# b6s.net
KiCad netlist of a schematic drawn in EasyEDA Pro
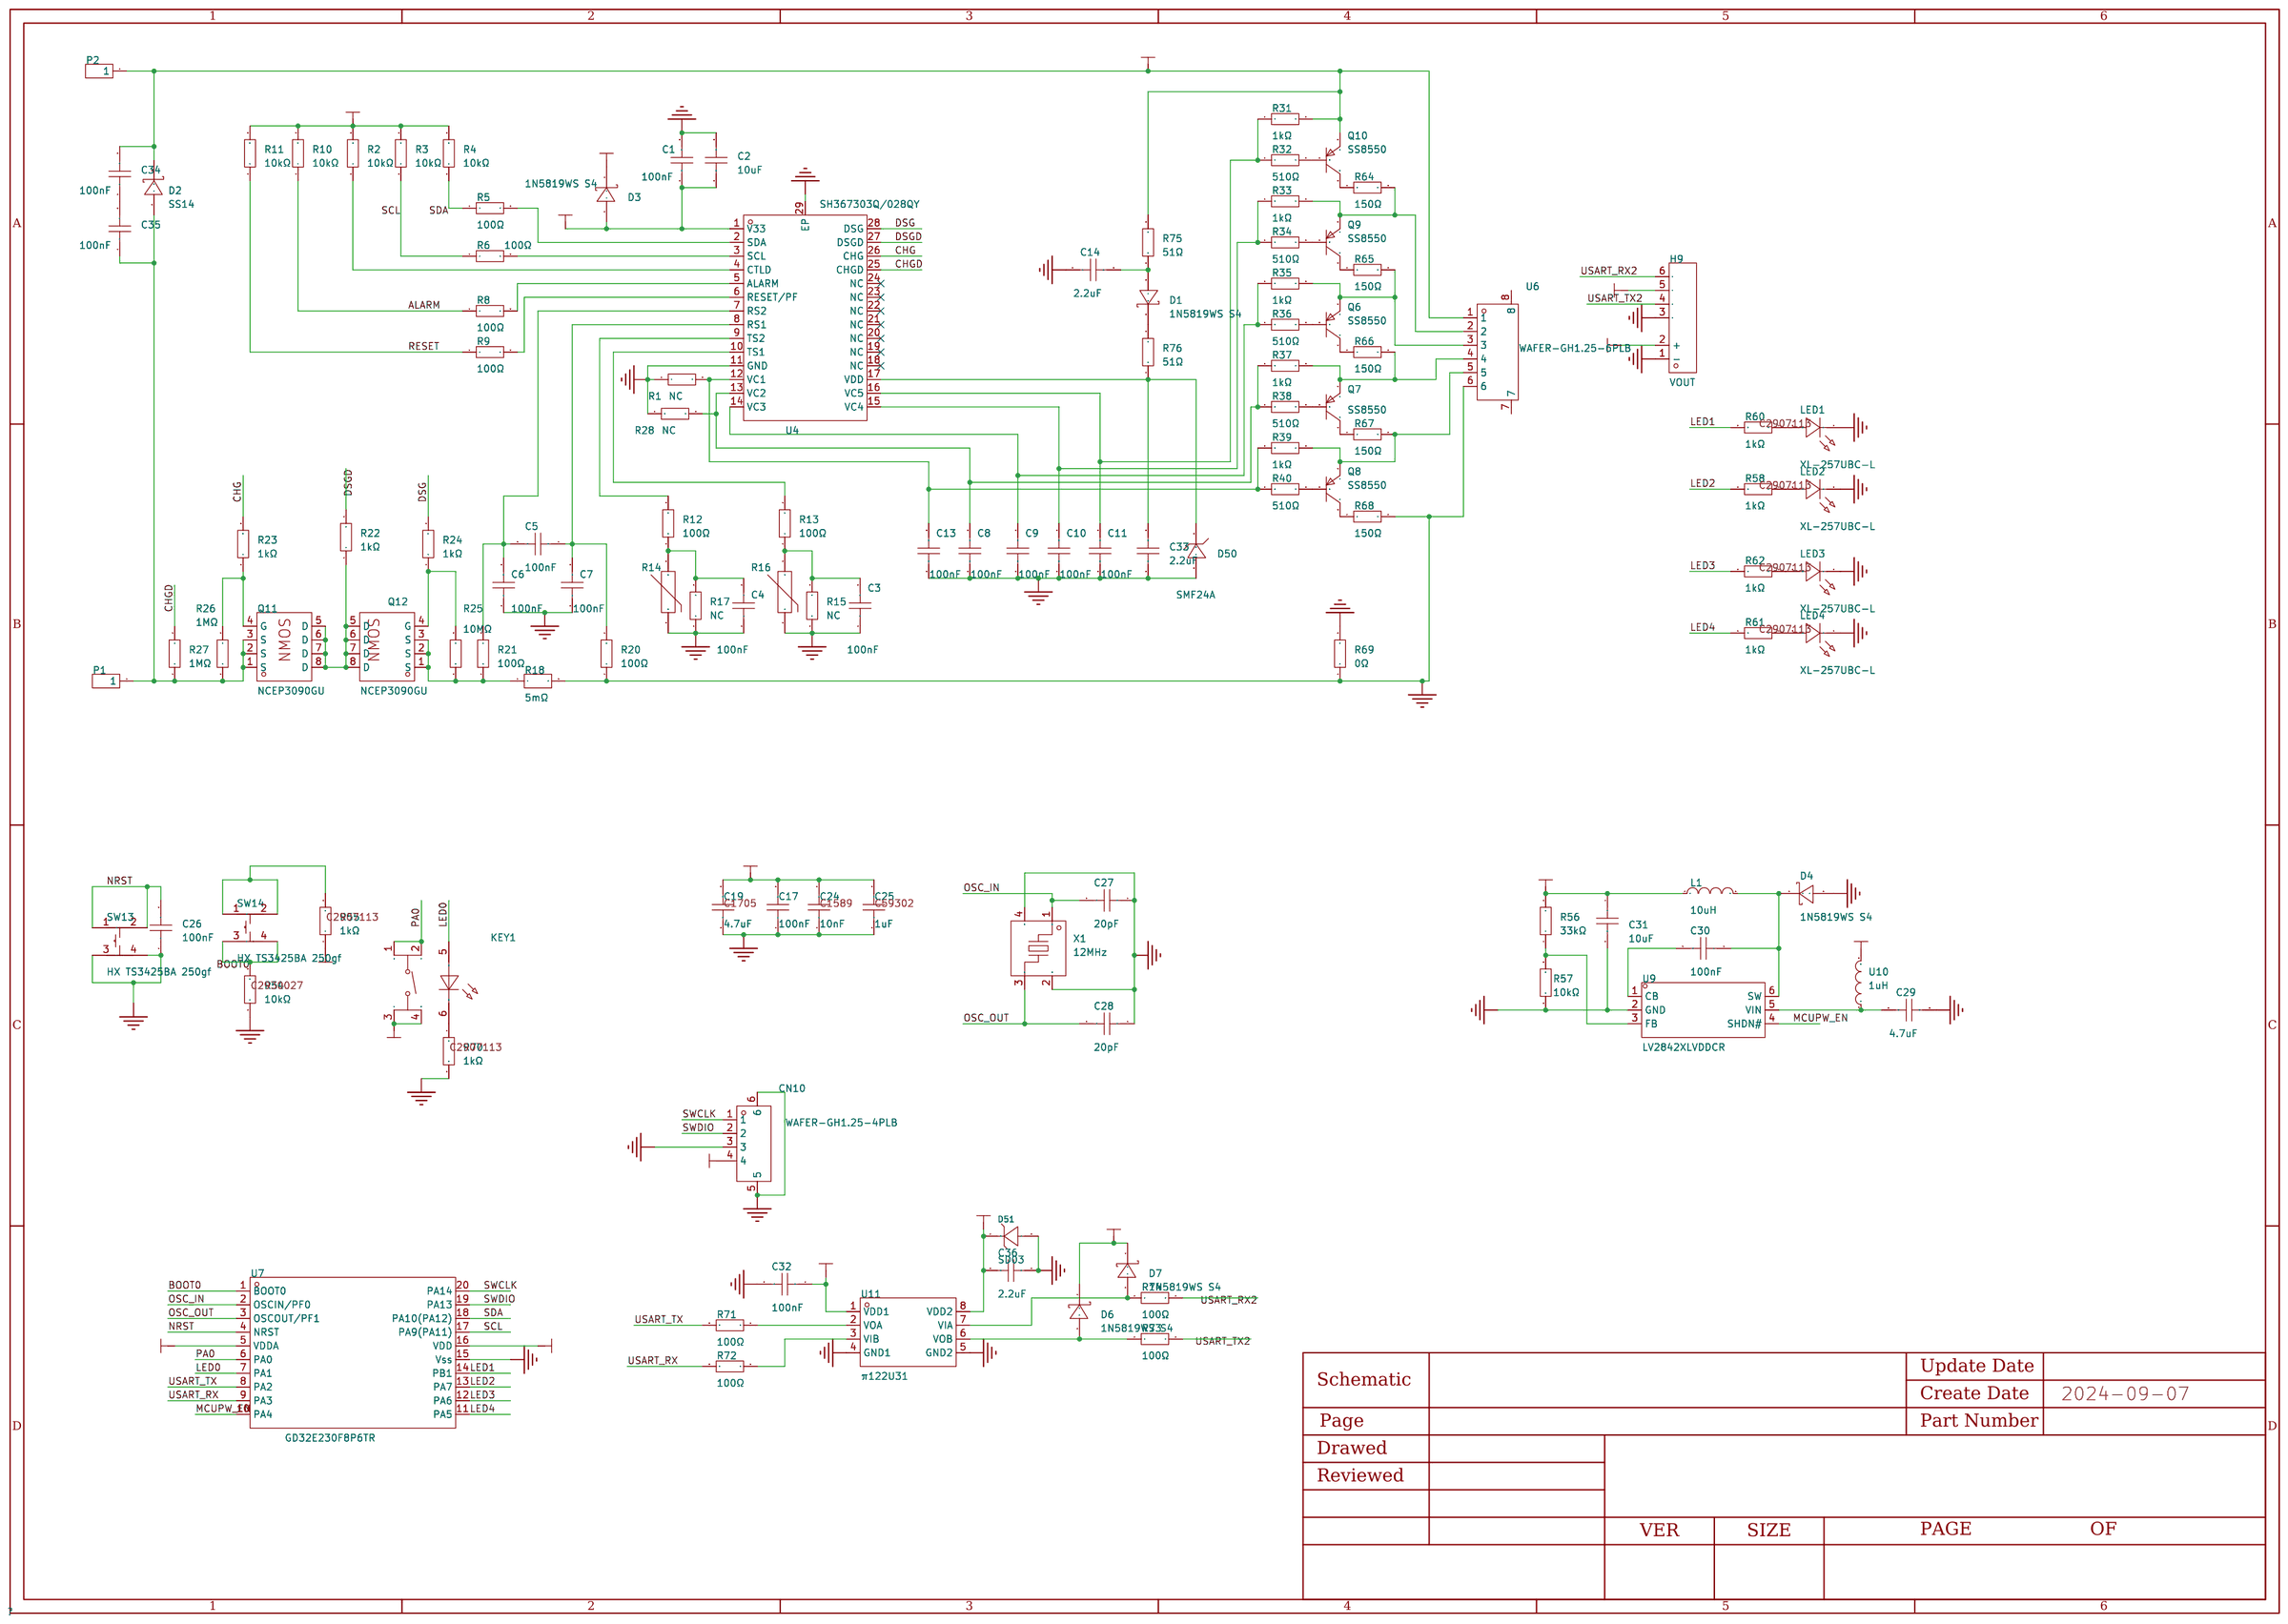
[diagram p0: schematic sheet]

(export (version "E")
  (design (tool "Eeschema 10.0.6"))
  (components
    (comp (ref "C1")
      (value "100nF")
      (footprint "easyedapro:C0603")
      (fields
        (field (name "Manufacturer Part") "CC0603KRX7R9BB104")
        (field (name "Manufacturer") "YAGEO(国巨)")
      )
      (libsource (lib "easyedapro") (part "CapAcitance"))
    )
    (comp (ref "C2")
      (value "10uF")
      (footprint "easyedapro:C0603")
      (fields
        (field (name "Manufacturer Part") "CL10A106MP8NNNC")
        (field (name "Manufacturer") "SAMSUNG(三星)")
      )
      (libsource (lib "easyedapro") (part "CapAcitance"))
    )
    (comp (ref "C3")
      (value "100nF")
      (footprint "easyedapro:C0603")
      (fields
        (field (name "Manufacturer Part") "CC0603KRX7R9BB104")
        (field (name "Manufacturer") "YAGEO(国巨)")
      )
      (libsource (lib "easyedapro") (part "CapAcitance"))
    )
    (comp (ref "C4")
      (value "100nF")
      (footprint "easyedapro:C0603")
      (fields
        (field (name "Manufacturer Part") "CC0603KRX7R9BB104")
        (field (name "Manufacturer") "YAGEO(国巨)")
      )
      (libsource (lib "easyedapro") (part "CapAcitance"))
    )
    (comp (ref "C5")
      (value "100nF")
      (footprint "easyedapro:C0603")
      (fields
        (field (name "Manufacturer Part") "CC0603KRX7R9BB104")
        (field (name "Manufacturer") "YAGEO(国巨)")
      )
      (libsource (lib "easyedapro") (part "CapAcitance"))
    )
    (comp (ref "C6")
      (value "100nF")
      (footprint "easyedapro:C0603")
      (fields
        (field (name "Manufacturer Part") "CC0603KRX7R9BB104")
        (field (name "Manufacturer") "YAGEO(国巨)")
      )
      (libsource (lib "easyedapro") (part "CapAcitance"))
    )
    (comp (ref "C7")
      (value "100nF")
      (footprint "easyedapro:C0603")
      (fields
        (field (name "Manufacturer Part") "CC0603KRX7R9BB104")
        (field (name "Manufacturer") "YAGEO(国巨)")
      )
      (libsource (lib "easyedapro") (part "CapAcitance"))
    )
    (comp (ref "C8")
      (value "100nF")
      (footprint "easyedapro:C0603")
      (fields
        (field (name "Manufacturer Part") "CC0603KRX7R9BB104")
        (field (name "Manufacturer") "YAGEO(国巨)")
      )
      (libsource (lib "easyedapro") (part "CapAcitance"))
    )
    (comp (ref "C9")
      (value "100nF")
      (footprint "easyedapro:C0603")
      (fields
        (field (name "Manufacturer Part") "CC0603KRX7R9BB104")
        (field (name "Manufacturer") "YAGEO(国巨)")
      )
      (libsource (lib "easyedapro") (part "CapAcitance"))
    )
    (comp (ref "C10")
      (value "100nF")
      (footprint "easyedapro:C0603")
      (fields
        (field (name "Manufacturer Part") "CC0603KRX7R9BB104")
        (field (name "Manufacturer") "YAGEO(国巨)")
      )
      (libsource (lib "easyedapro") (part "CapAcitance"))
    )
    (comp (ref "C11")
      (value "100nF")
      (footprint "easyedapro:C0603")
      (fields
        (field (name "Manufacturer Part") "CC0603KRX7R9BB104")
        (field (name "Manufacturer") "YAGEO(国巨)")
      )
      (libsource (lib "easyedapro") (part "CapAcitance"))
    )
    (comp (ref "C13")
      (value "100nF")
      (footprint "easyedapro:C0603")
      (fields
        (field (name "Manufacturer Part") "CC0603KRX7R9BB104")
        (field (name "Manufacturer") "YAGEO(国巨)")
      )
      (libsource (lib "easyedapro") (part "CapAcitance"))
    )
    (comp (ref "C14")
      (value "2.2uF")
      (footprint "easyedapro:C0603")
      (fields
        (field (name "Manufacturer Part") "CL21A225KBQNNNE")
        (field (name "Manufacturer") "SAMSUNG(三星)")
      )
      (libsource (lib "easyedapro") (part "CapAcitance"))
    )
    (comp (ref "C17")
      (value "100nF")
      (footprint "easyedapro:C0603")
      (fields
        (field (name "Manufacturer Part") "CC0603KRX7R9BB104")
        (field (name "Manufacturer") "YAGEO(国巨)")
      )
      (libsource (lib "easyedapro") (part "CapAcitance"))
    )
    (comp (ref "C19")
      (value "4.7uF")
      (footprint "easyedapro:C0603")
      (fields
        (field (name "Manufacturer Part") "CL10A475KP8NNNC")
        (field (name "Manufacturer") "SAMSUNG(三星)")
        (field (name "Supplier Part") "C1705")
      )
      (libsource (lib "easyedapro") (part "CapAcitance"))
    )
    (comp (ref "C24")
      (value "10nF")
      (footprint "easyedapro:C0603")
      (fields
        (field (name "Manufacturer Part") "CL10B103KB8NNNC")
        (field (name "Manufacturer") "SAMSUNG(三星)")
        (field (name "Supplier Part") "C1589")
      )
      (libsource (lib "easyedapro") (part "CapAcitance"))
    )
    (comp (ref "C25")
      (value "1uF")
      (footprint "easyedapro:C0603")
      (fields
        (field (name "Manufacturer Part") "0603B105K250NT")
        (field (name "Manufacturer") "FH(风华)")
        (field (name "Supplier Part") "C59302")
      )
      (libsource (lib "easyedapro") (part "CapAcitance"))
    )
    (comp (ref "C26")
      (value "100nF")
      (footprint "easyedapro:C0603")
      (fields
        (field (name "Manufacturer Part") "CC0603KRX7R9BB104")
        (field (name "Manufacturer") "YAGEO(国巨)")
      )
      (libsource (lib "easyedapro") (part "CapAcitance"))
    )
    (comp (ref "C27")
      (value "20pF")
      (footprint "easyedapro:C0603")
      (fields (field (name "Manufacturer Part") "0603CG200J500NT") (field (name "Manufacturer") "FH(风华)"))
      (libsource (lib "easyedapro") (part "CapAcitance"))
    )
    (comp (ref "C28")
      (value "20pF")
      (footprint "easyedapro:C0603")
      (fields (field (name "Manufacturer Part") "0603CG200J500NT") (field (name "Manufacturer") "FH(风华)"))
      (libsource (lib "easyedapro") (part "CapAcitance"))
    )
    (comp (ref "C29")
      (value "4.7uF")
      (footprint "easyedapro:C0603")
      (fields
        (field (name "Manufacturer Part") "CGA0805X7R475K350MT")
        (field (name "Manufacturer") "HRE(芯声)")
      )
      (libsource (lib "easyedapro") (part "CapAcitance"))
    )
    (comp (ref "C30")
      (value "100nF")
      (footprint "easyedapro:C0603")
      (fields
        (field (name "Manufacturer Part") "CC0603KRX7R9BB104")
        (field (name "Manufacturer") "YAGEO(国巨)")
      )
      (libsource (lib "easyedapro") (part "CapAcitance"))
    )
    (comp (ref "C31")
      (value "10uF")
      (footprint "easyedapro:C0603")
      (fields
        (field (name "Manufacturer Part") "CL10A106MP8NNNC")
        (field (name "Manufacturer") "SAMSUNG(三星)")
      )
      (libsource (lib "easyedapro") (part "CapAcitance"))
    )
    (comp (ref "C32")
      (value "100nF")
      (footprint "easyedapro:C0603")
      (fields
        (field (name "Manufacturer Part") "CC0603KRX7R9BB104")
        (field (name "Manufacturer") "YAGEO(国巨)")
      )
      (libsource (lib "easyedapro") (part "CapAcitance"))
    )
    (comp (ref "C33")
      (value "2.2uF")
      (footprint "easyedapro:C0603")
      (fields
        (field (name "Manufacturer Part") "CL21A225KBQNNNE")
        (field (name "Manufacturer") "SAMSUNG(三星)")
      )
      (libsource (lib "easyedapro") (part "CapAcitance"))
    )
    (comp (ref "C34")
      (value "100nF")
      (footprint "easyedapro:C0603")
      (fields
        (field (name "Manufacturer Part") "CC0603KRX7R9BB104")
        (field (name "Manufacturer") "YAGEO(国巨)")
      )
      (libsource (lib "easyedapro") (part "CapAcitance"))
    )
    (comp (ref "C35")
      (value "100nF")
      (footprint "easyedapro:C0603")
      (fields
        (field (name "Manufacturer Part") "CC0603KRX7R9BB104")
        (field (name "Manufacturer") "YAGEO(国巨)")
      )
      (libsource (lib "easyedapro") (part "CapAcitance"))
    )
    (comp (ref "C36")
      (value "2.2uF")
      (footprint "easyedapro:C0603")
      (fields
        (field (name "Manufacturer Part") "CL10A225KP8NNNC")
        (field (name "Manufacturer") "SAMSUNG(三星)")
      )
      (libsource (lib "easyedapro") (part "CapAcitance"))
    )
    (comp (ref "CN10")
      (value "WAFER-GH1.25-4PLB")
      (footprint "easyedapro:CONN-SMD_4P-P1.25_XUNPU_WAFER-GH1.25-4PLB")
      (description "插针结构:1x4P;间距:1.25mm;安装方式:立贴;参考系列:GH;总PIN数:4P;排数:1;每排PIN数:4;额定电流:1A;工作温度范围:-25°C~+85°C;")
      (fields (field (name "Manufacturer") "XUNPU(讯普)"))
      (libsource (lib "easyedapro") (part "WAFER-GH1.25-4PLB"))
    )
    (comp (ref "D1")
      (value "1N5819WS S4")
      (footprint "easyedapro:SOD-323_L1.8-W1.3-LS2.5-RD")
      (description "正向压降(Vf):600mV@1A;直流反向耐压(Vr):40V;平均整流电流(Io):1A;")
      (fields (field (name "Manufacturer") "JSMSEMI(杰盛微)"))
      (libsource (lib "easyedapro") (part "1N5819WS"))
    )
    (comp (ref "D2")
      (value "SS14")
      (footprint "easyedapro:SMA_L4.2-W2.6-LS5.3-RD")
      (description "二极管配置:独立式;正向压降(Vf):550mV@1A;直流反向耐压(Vr):40V;整流电流:1A;")
      (fields (field (name "Manufacturer") "MDD(辰达半导体)"))
      (libsource (lib "easyedapro") (part "SS14"))
    )
    (comp (ref "D3")
      (value "1N5819WS S4")
      (footprint "easyedapro:SOD-323_L1.8-W1.3-LS2.5-RD")
      (description "正向压降(Vf):600mV@1A;直流反向耐压(Vr):40V;平均整流电流(Io):1A;")
      (fields (field (name "Manufacturer") "JSMSEMI(杰盛微)"))
      (libsource (lib "easyedapro") (part "1N5819WS"))
    )
    (comp (ref "D4")
      (value "1N5819WS S4")
      (footprint "easyedapro:SOD-323_L1.8-W1.3-LS2.5-RD")
      (description "正向压降(Vf):600mV@1A;直流反向耐压(Vr):40V;平均整流电流(Io):1A;")
      (fields (field (name "Manufacturer") "JSMSEMI(杰盛微)"))
      (libsource (lib "easyedapro") (part "1N5819WS"))
    )
    (comp (ref "D6")
      (value "1N5819WS S4")
      (footprint "easyedapro:SOD-323_L1.8-W1.3-LS2.5-RD")
      (description "正向压降(Vf):600mV@1A;直流反向耐压(Vr):40V;平均整流电流(Io):1A;")
      (fields (field (name "Manufacturer") "JSMSEMI(杰盛微)"))
      (libsource (lib "easyedapro") (part "1N5819WS"))
    )
    (comp (ref "D7")
      (value "1N5819WS S4")
      (footprint "easyedapro:SOD-323_L1.8-W1.3-LS2.5-RD")
      (description "正向压降(Vf):600mV@1A;直流反向耐压(Vr):40V;平均整流电流(Io):1A;")
      (fields (field (name "Manufacturer") "JSMSEMI(杰盛微)"))
      (libsource (lib "easyedapro") (part "1N5819WS"))
    )
    (comp (ref "D50")
      (value "SMF24A")
      (footprint "easyedapro:SOD-123FL_L2.8-W1.9-LS3.7-RD")
      (description "反向截止电压(Vrwm):22V;最大钳位电压:35.5V;峰值脉冲电流(Ipp)@10/1000us:5.6A;击穿电压:24.4V;")
      (fields (field (name "Manufacturer") "TWGMC(台湾迪嘉)"))
      (libsource (lib "easyedapro") (part "SMF22A_C2943862"))
    )
    (comp (ref "D51")
      (value "SD03")
      (footprint "easyedapro:SOD-323_L1.8-W1.3-LS2.5-RD")
      (description "反向截止电压(Vrwm):3.3V;最大钳位电压:14V;峰值脉冲电流(Ipp)@10/1000us:20A;击穿电压:4V;")
      (fields (field (name "Manufacturer") "MDD"))
      (libsource (lib "easyedapro") (part "SD03_C502526"))
    )
    (comp (ref "H9")
      (value "VOUT")
      (footprint "easyedapro:AMSS_XT60_2+4")
      (libsource (lib "easyedapro") (part "AMSS_XT60_2+4"))
    )
    (comp (ref "KEY1")
      (value "~")
      (footprint "easyedapro:LED_BUTTON")
      (libsource (lib "easyedapro") (part "LED_BUTTON"))
    )
    (comp (ref "L1")
      (value "10uH")
      (footprint "easyedapro:L1206")
      (description "电感值:1uH;精度:±20%;额定电流:1.2A;饱和电流(Isat):-;直流电阻(DCR):150mΩ;")
      (fields (field (name "Manufacturer Part") "CMI321609X100KT") (field (name "Manufacturer") "FH(风华)"))
      (libsource (lib "easyedapro") (part "CMP321609UD1R0MT"))
    )
    (comp (ref "LED1")
      (value "XL-257UBC-L")
      (footprint "easyedapro:LED-TH_L5.0-W2.5-P2.54-FD_GREEN_XL-257SYGD-L")
      (fields (field (name "Manufacturer") "XINGLIGHT(成兴光)"))
      (libsource (lib "easyedapro") (part "XL-257UBC-L"))
    )
    (comp (ref "LED2")
      (value "XL-257UBC-L")
      (footprint "easyedapro:LED-TH_L5.0-W2.5-P2.54-FD_GREEN_XL-257SYGD-L")
      (fields (field (name "Manufacturer") "XINGLIGHT(成兴光)"))
      (libsource (lib "easyedapro") (part "XL-257UBC-L"))
    )
    (comp (ref "LED3")
      (value "XL-257UBC-L")
      (footprint "easyedapro:LED-TH_L5.0-W2.5-P2.54-FD_GREEN_XL-257SYGD-L")
      (fields (field (name "Manufacturer") "XINGLIGHT(成兴光)"))
      (libsource (lib "easyedapro") (part "XL-257UBC-L"))
    )
    (comp (ref "LED4")
      (value "XL-257UBC-L")
      (footprint "easyedapro:LED-TH_L5.0-W2.5-P2.54-FD_GREEN_XL-257SYGD-L")
      (fields (field (name "Manufacturer") "XINGLIGHT(成兴光)"))
      (libsource (lib "easyedapro") (part "XL-257UBC-L"))
    )
    (comp (ref "P1")
      (value "~")
      (footprint "easyedapro:Wire_14AWG")
      (libsource (lib "easyedapro") (part "Wire_14AWG"))
    )
    (comp (ref "P2")
      (value "~")
      (footprint "easyedapro:Wire_14AWG")
      (libsource (lib "easyedapro") (part "Wire_14AWG"))
    )
    (comp (ref "Q6")
      (value "SS8550")
      (footprint "easyedapro:SOT-23-3_L2.9-W1.3-P1.90-LS2.4-BR")
      (description "晶体管类型:PNP;集电极电流(Ic):1.5A;集射极击穿电压(Vceo):25V;功率(Pd):300mW;直流电流增益(hFE@Ic,Vce):120@100mA,1.0V;")
      (fields (field (name "Manufacturer") "宏迦橙"))
      (libsource (lib "easyedapro") (part "SS8550_C7420371"))
    )
    (comp (ref "Q7")
      (value "SS8550")
      (footprint "easyedapro:SOT-23-3_L2.9-W1.3-P1.90-LS2.4-BR")
      (description "晶体管类型:PNP;集电极电流(Ic):1.5A;集射极击穿电压(Vceo):25V;功率(Pd):300mW;直流电流增益(hFE@Ic,Vce):120@100mA,1.0V;")
      (fields (field (name "Manufacturer") "宏迦橙"))
      (libsource (lib "easyedapro") (part "SS8550_C7420371"))
    )
    (comp (ref "Q8")
      (value "SS8550")
      (footprint "easyedapro:SOT-23-3_L2.9-W1.3-P1.90-LS2.4-BR")
      (description "晶体管类型:PNP;集电极电流(Ic):1.5A;集射极击穿电压(Vceo):25V;功率(Pd):300mW;直流电流增益(hFE@Ic,Vce):120@100mA,1.0V;")
      (fields (field (name "Manufacturer") "宏迦橙"))
      (libsource (lib "easyedapro") (part "SS8550_C7420371"))
    )
    (comp (ref "Q9")
      (value "SS8550")
      (footprint "easyedapro:SOT-23-3_L2.9-W1.3-P1.90-LS2.4-BR")
      (description "晶体管类型:PNP;集电极电流(Ic):1.5A;集射极击穿电压(Vceo):25V;功率(Pd):300mW;直流电流增益(hFE@Ic,Vce):120@100mA,1.0V;")
      (fields (field (name "Manufacturer") "宏迦橙"))
      (libsource (lib "easyedapro") (part "SS8550_C7420371"))
    )
    (comp (ref "Q10")
      (value "SS8550")
      (footprint "easyedapro:SOT-23-3_L2.9-W1.3-P1.90-LS2.4-BR")
      (description "晶体管类型:PNP;集电极电流(Ic):1.5A;集射极击穿电压(Vceo):25V;功率(Pd):300mW;直流电流增益(hFE@Ic,Vce):120@100mA,1.0V;")
      (fields (field (name "Manufacturer") "宏迦橙"))
      (libsource (lib "easyedapro") (part "SS8550_C7420371"))
    )
    (comp (ref "Q11")
      (value "NCEP3090GU")
      (footprint "easyedapro:DFN-8_L5.8-W4.9-P1.27-LS6.1-BL-2")
      (fields (field (name "Manufacturer") "NCE(无锡新洁能)"))
      (libsource (lib "easyedapro") (part "NCEP3090GU"))
    )
    (comp (ref "Q12")
      (value "NCEP3090GU")
      (footprint "easyedapro:DFN-8_L5.8-W4.9-P1.27-LS6.1-BL-2")
      (fields (field (name "Manufacturer") "NCE(无锡新洁能)"))
      (libsource (lib "easyedapro") (part "NCEP3090GU"))
    )
    (comp (ref "R1") (value "NC") (footprint "easyedapro:R0805") (libsource (lib "easyedapro") (part "电阻")))
    (comp (ref "R2")
      (value "10kΩ")
      (footprint "easyedapro:R0805")
      (fields (field (name "Manufacturer Part") "FRC0603J103TS") (field (name "Manufacturer") "FOJAN(富捷)"))
      (libsource (lib "easyedapro") (part "电阻"))
    )
    (comp (ref "R3")
      (value "10kΩ")
      (footprint "easyedapro:R0805")
      (fields (field (name "Manufacturer Part") "FRC0603J103TS") (field (name "Manufacturer") "FOJAN(富捷)"))
      (libsource (lib "easyedapro") (part "电阻"))
    )
    (comp (ref "R4")
      (value "10kΩ")
      (footprint "easyedapro:R0805")
      (fields (field (name "Manufacturer Part") "FRC0603J103TS") (field (name "Manufacturer") "FOJAN(富捷)"))
      (libsource (lib "easyedapro") (part "电阻"))
    )
    (comp (ref "R5")
      (value "100Ω")
      (footprint "easyedapro:R0805")
      (fields (field (name "Manufacturer Part") "RC0603FR-07100RL") (field (name "Manufacturer") "YAGEO(国巨)"))
      (libsource (lib "easyedapro") (part "电阻"))
    )
    (comp (ref "R6")
      (value "100Ω")
      (footprint "easyedapro:R0805")
      (fields (field (name "Manufacturer Part") "RC0603FR-07100RL") (field (name "Manufacturer") "YAGEO(国巨)"))
      (libsource (lib "easyedapro") (part "电阻"))
    )
    (comp (ref "R8")
      (value "100Ω")
      (footprint "easyedapro:R0805")
      (fields (field (name "Manufacturer Part") "RC0603FR-07100RL") (field (name "Manufacturer") "YAGEO(国巨)"))
      (libsource (lib "easyedapro") (part "电阻"))
    )
    (comp (ref "R9")
      (value "100Ω")
      (footprint "easyedapro:R0805")
      (fields (field (name "Manufacturer Part") "RC0603FR-07100RL") (field (name "Manufacturer") "YAGEO(国巨)"))
      (libsource (lib "easyedapro") (part "电阻"))
    )
    (comp (ref "R10")
      (value "10kΩ")
      (footprint "easyedapro:R0805")
      (fields (field (name "Manufacturer Part") "FRC0603J103TS") (field (name "Manufacturer") "FOJAN(富捷)"))
      (libsource (lib "easyedapro") (part "电阻"))
    )
    (comp (ref "R11")
      (value "10kΩ")
      (footprint "easyedapro:R0805")
      (fields (field (name "Manufacturer Part") "FRC0603J103TS") (field (name "Manufacturer") "FOJAN(富捷)"))
      (libsource (lib "easyedapro") (part "电阻"))
    )
    (comp (ref "R12")
      (value "100Ω")
      (footprint "easyedapro:R0805")
      (fields (field (name "Manufacturer Part") "RC0603FR-07100RL") (field (name "Manufacturer") "YAGEO(国巨)"))
      (libsource (lib "easyedapro") (part "电阻"))
    )
    (comp (ref "R13")
      (value "100Ω")
      (footprint "easyedapro:R0805")
      (fields (field (name "Manufacturer Part") "RC0603FR-07100RL") (field (name "Manufacturer") "YAGEO(国巨)"))
      (libsource (lib "easyedapro") (part "电阻"))
    )
    (comp (ref "R14")
      (value "MF52A103F3950 (A1)")
      (footprint "easyedapro:RES-TH_L2.5-W2.5-P1.70-D0.3")
      (description "阻值(25°C):10kΩ;B值(25°C/50°C):3950K;电阻精度:±1%;功率:50mW;B值精度:±1%;最大稳态电流(25°C):-;")
      (fields (field (name "Manufacturer") "时恒"))
      (libsource (lib "easyedapro") (part "MF52A1103F3950(P334-4)"))
    )
    (comp (ref "R15") (value "NC") (footprint "easyedapro:R0805") (libsource (lib "easyedapro") (part "电阻")))
    (comp (ref "R16")
      (value "MF52A103F3950 (A1)")
      (footprint "easyedapro:RES-TH_L2.5-W2.5-P1.70-D0.3")
      (description "阻值(25°C):10kΩ;B值(25°C/50°C):3950K;电阻精度:±1%;功率:50mW;B值精度:±1%;最大稳态电流(25°C):-;")
      (fields (field (name "Manufacturer") "时恒"))
      (libsource (lib "easyedapro") (part "MF52A1103F3950(P334-4)"))
    )
    (comp (ref "R17") (value "NC") (footprint "easyedapro:R0805") (libsource (lib "easyedapro") (part "电阻")))
    (comp (ref "R18")
      (value "5mΩ")
      (footprint "easyedapro:RES-SMD_L6.4-W3.2-1")
      (description "电阻类型:采样电阻;阻值:5mΩ;精度:±1%;额定压降:-;功率:3W;温度系数:±50ppm/°C;安装方式:贴片;")
      (fields
        (field (name "Manufacturer Part") "HoLLR1206-1W-5mR-1%")
        (field (name "Manufacturer") "Milliohm(毫欧)")
      )
      (libsource (lib "easyedapro") (part "HOLLR2512-3W-5MR-1%"))
    )
    (comp (ref "R20")
      (value "100Ω")
      (footprint "easyedapro:R0805")
      (fields (field (name "Manufacturer Part") "RC0603FR-07100RL") (field (name "Manufacturer") "YAGEO(国巨)"))
      (libsource (lib "easyedapro") (part "电阻"))
    )
    (comp (ref "R21")
      (value "100Ω")
      (footprint "easyedapro:R0805")
      (fields (field (name "Manufacturer Part") "RC0603FR-07100RL") (field (name "Manufacturer") "YAGEO(国巨)"))
      (libsource (lib "easyedapro") (part "电阻"))
    )
    (comp (ref "R22")
      (value "1kΩ")
      (footprint "easyedapro:R0805")
      (fields (field (name "Manufacturer Part") "FRC0603J102 TS") (field (name "Manufacturer") "FOJAN(富捷)"))
      (libsource (lib "easyedapro") (part "电阻"))
    )
    (comp (ref "R23")
      (value "1kΩ")
      (footprint "easyedapro:R0805")
      (fields (field (name "Manufacturer Part") "FRC0603J102 TS") (field (name "Manufacturer") "FOJAN(富捷)"))
      (libsource (lib "easyedapro") (part "电阻"))
    )
    (comp (ref "R24")
      (value "1kΩ")
      (footprint "easyedapro:R0805")
      (fields (field (name "Manufacturer Part") "FRC0603J102 TS") (field (name "Manufacturer") "FOJAN(富捷)"))
      (libsource (lib "easyedapro") (part "电阻"))
    )
    (comp (ref "R25")
      (value "10MΩ")
      (footprint "easyedapro:R0805")
      (fields
        (field (name "Manufacturer Part") "0603WAJ0106T5E")
        (field (name "Manufacturer") "UNI-ROYAL(厚声)")
      )
      (libsource (lib "easyedapro") (part "电阻"))
    )
    (comp (ref "R26")
      (value "1MΩ")
      (footprint "easyedapro:R0805")
      (fields
        (field (name "Manufacturer Part") "0603WAJ0105T5E")
        (field (name "Manufacturer") "UNI-ROYAL(厚声)")
      )
      (libsource (lib "easyedapro") (part "电阻"))
    )
    (comp (ref "R27")
      (value "1MΩ")
      (footprint "easyedapro:R0805")
      (fields
        (field (name "Manufacturer Part") "0603WAJ0105T5E")
        (field (name "Manufacturer") "UNI-ROYAL(厚声)")
      )
      (libsource (lib "easyedapro") (part "电阻"))
    )
    (comp (ref "R28") (value "NC") (footprint "easyedapro:R0805") (libsource (lib "easyedapro") (part "电阻")))
    (comp (ref "R31")
      (value "1kΩ")
      (footprint "easyedapro:R0805")
      (fields (field (name "Manufacturer Part") "FRC0603J102 TS") (field (name "Manufacturer") "FOJAN(富捷)"))
      (libsource (lib "easyedapro") (part "电阻"))
    )
    (comp (ref "R32")
      (value "510Ω")
      (footprint "easyedapro:R0805")
      (fields (field (name "Manufacturer Part") "FRC0603J511 TS") (field (name "Manufacturer") "FOJAN(富捷)"))
      (libsource (lib "easyedapro") (part "电阻"))
    )
    (comp (ref "R33")
      (value "1kΩ")
      (footprint "easyedapro:R0805")
      (fields (field (name "Manufacturer Part") "FRC0603J102 TS") (field (name "Manufacturer") "FOJAN(富捷)"))
      (libsource (lib "easyedapro") (part "电阻"))
    )
    (comp (ref "R34")
      (value "510Ω")
      (footprint "easyedapro:R0805")
      (fields (field (name "Manufacturer Part") "FRC0603J511 TS") (field (name "Manufacturer") "FOJAN(富捷)"))
      (libsource (lib "easyedapro") (part "电阻"))
    )
    (comp (ref "R35")
      (value "1kΩ")
      (footprint "easyedapro:R0805")
      (fields (field (name "Manufacturer Part") "FRC0603J102 TS") (field (name "Manufacturer") "FOJAN(富捷)"))
      (libsource (lib "easyedapro") (part "电阻"))
    )
    (comp (ref "R36")
      (value "510Ω")
      (footprint "easyedapro:R0805")
      (fields (field (name "Manufacturer Part") "FRC0603J511 TS") (field (name "Manufacturer") "FOJAN(富捷)"))
      (libsource (lib "easyedapro") (part "电阻"))
    )
    (comp (ref "R37")
      (value "1kΩ")
      (footprint "easyedapro:R0805")
      (fields (field (name "Manufacturer Part") "FRC0603J102 TS") (field (name "Manufacturer") "FOJAN(富捷)"))
      (libsource (lib "easyedapro") (part "电阻"))
    )
    (comp (ref "R38")
      (value "510Ω")
      (footprint "easyedapro:R0805")
      (fields (field (name "Manufacturer Part") "FRC0603J511 TS") (field (name "Manufacturer") "FOJAN(富捷)"))
      (libsource (lib "easyedapro") (part "电阻"))
    )
    (comp (ref "R39")
      (value "1kΩ")
      (footprint "easyedapro:R0805")
      (fields (field (name "Manufacturer Part") "FRC0603J102 TS") (field (name "Manufacturer") "FOJAN(富捷)"))
      (libsource (lib "easyedapro") (part "电阻"))
    )
    (comp (ref "R40")
      (value "510Ω")
      (footprint "easyedapro:R0805")
      (fields (field (name "Manufacturer Part") "FRC0603J511 TS") (field (name "Manufacturer") "FOJAN(富捷)"))
      (libsource (lib "easyedapro") (part "电阻"))
    )
    (comp (ref "R54")
      (value "10kΩ")
      (footprint "easyedapro:R0805")
      (fields
        (field (name "Manufacturer Part") "FRC0603J103TS")
        (field (name "Manufacturer") "FOJAN(富捷)")
        (field (name "Supplier Part") "C2930027")
      )
      (libsource (lib "easyedapro") (part "电阻"))
    )
    (comp (ref "R55")
      (value "1kΩ")
      (footprint "easyedapro:R0805")
      (fields
        (field (name "Manufacturer Part") "FRC0603J102 TS")
        (field (name "Manufacturer") "FOJAN(富捷)")
        (field (name "Supplier Part") "C2907113")
      )
      (libsource (lib "easyedapro") (part "电阻"))
    )
    (comp (ref "R56")
      (value "33kΩ")
      (footprint "easyedapro:R0805")
      (fields
        (field (name "Manufacturer Part") "0603WAF3302T5E")
        (field (name "Manufacturer") "UNI-ROYAL(厚声)")
      )
      (libsource (lib "easyedapro") (part "电阻"))
    )
    (comp (ref "R57")
      (value "10kΩ")
      (footprint "easyedapro:R0805")
      (fields (field (name "Manufacturer Part") "RC0603FR-0710KL") (field (name "Manufacturer") "YAGEO(国巨)"))
      (libsource (lib "easyedapro") (part "电阻"))
    )
    (comp (ref "R58")
      (value "1kΩ")
      (footprint "easyedapro:R0805")
      (fields
        (field (name "Manufacturer Part") "FRC0603J102 TS")
        (field (name "Manufacturer") "FOJAN(富捷)")
        (field (name "Supplier Part") "C2907113")
      )
      (libsource (lib "easyedapro") (part "电阻"))
    )
    (comp (ref "R60")
      (value "1kΩ")
      (footprint "easyedapro:R0805")
      (fields
        (field (name "Manufacturer Part") "FRC0603J102 TS")
        (field (name "Manufacturer") "FOJAN(富捷)")
        (field (name "Supplier Part") "C2907113")
      )
      (libsource (lib "easyedapro") (part "电阻"))
    )
    (comp (ref "R61")
      (value "1kΩ")
      (footprint "easyedapro:R0805")
      (fields
        (field (name "Manufacturer Part") "FRC0603J102 TS")
        (field (name "Manufacturer") "FOJAN(富捷)")
        (field (name "Supplier Part") "C2907113")
      )
      (libsource (lib "easyedapro") (part "电阻"))
    )
    (comp (ref "R62")
      (value "1kΩ")
      (footprint "easyedapro:R0805")
      (fields
        (field (name "Manufacturer Part") "FRC0603J102 TS")
        (field (name "Manufacturer") "FOJAN(富捷)")
        (field (name "Supplier Part") "C2907113")
      )
      (libsource (lib "easyedapro") (part "电阻"))
    )
    (comp (ref "R64")
      (value "150Ω")
      (footprint "easyedapro:R0805")
      (fields (field (name "Manufacturer Part") "FRC1206J151 TS") (field (name "Manufacturer") "FOJAN(富捷)"))
      (libsource (lib "easyedapro") (part "电阻"))
    )
    (comp (ref "R65")
      (value "150Ω")
      (footprint "easyedapro:R0805")
      (fields (field (name "Manufacturer Part") "FRC1206J151 TS") (field (name "Manufacturer") "FOJAN(富捷)"))
      (libsource (lib "easyedapro") (part "电阻"))
    )
    (comp (ref "R66")
      (value "150Ω")
      (footprint "easyedapro:R0805")
      (fields (field (name "Manufacturer Part") "FRC1206J151 TS") (field (name "Manufacturer") "FOJAN(富捷)"))
      (libsource (lib "easyedapro") (part "电阻"))
    )
    (comp (ref "R67")
      (value "150Ω")
      (footprint "easyedapro:R0805")
      (fields (field (name "Manufacturer Part") "FRC1206J151 TS") (field (name "Manufacturer") "FOJAN(富捷)"))
      (libsource (lib "easyedapro") (part "电阻"))
    )
    (comp (ref "R68")
      (value "150Ω")
      (footprint "easyedapro:R0805")
      (fields (field (name "Manufacturer Part") "FRC1206J151 TS") (field (name "Manufacturer") "FOJAN(富捷)"))
      (libsource (lib "easyedapro") (part "电阻"))
    )
    (comp (ref "R69")
      (value "0Ω")
      (footprint "easyedapro:R0805")
      (fields
        (field (name "Manufacturer Part") "0603WAF0000T5E")
        (field (name "Manufacturer") "UNI-ROYAL(厚声)")
      )
      (libsource (lib "easyedapro") (part "电阻"))
    )
    (comp (ref "R70")
      (value "1kΩ")
      (footprint "easyedapro:R0805")
      (fields
        (field (name "Manufacturer Part") "FRC0603J102 TS")
        (field (name "Manufacturer") "FOJAN(富捷)")
        (field (name "Supplier Part") "C2907113")
      )
      (libsource (lib "easyedapro") (part "电阻"))
    )
    (comp (ref "R71")
      (value "100Ω")
      (footprint "easyedapro:R0805")
      (fields (field (name "Manufacturer Part") "RC0603FR-07100RL") (field (name "Manufacturer") "YAGEO(国巨)"))
      (libsource (lib "easyedapro") (part "电阻"))
    )
    (comp (ref "R72")
      (value "100Ω")
      (footprint "easyedapro:R0805")
      (fields (field (name "Manufacturer Part") "RC0603FR-07100RL") (field (name "Manufacturer") "YAGEO(国巨)"))
      (libsource (lib "easyedapro") (part "电阻"))
    )
    (comp (ref "R73")
      (value "100Ω")
      (footprint "easyedapro:R0805")
      (fields (field (name "Manufacturer Part") "RC0603FR-07100RL") (field (name "Manufacturer") "YAGEO(国巨)"))
      (libsource (lib "easyedapro") (part "电阻"))
    )
    (comp (ref "R74")
      (value "100Ω")
      (footprint "easyedapro:R0805")
      (fields (field (name "Manufacturer Part") "RC0603FR-07100RL") (field (name "Manufacturer") "YAGEO(国巨)"))
      (libsource (lib "easyedapro") (part "电阻"))
    )
    (comp (ref "R75")
      (value "51Ω")
      (footprint "easyedapro:R0805")
      (description "电阻类型:厚膜电阻;阻值:51Ω;精度:±1%;功率:125mW;最大工作电压:150V;温度系数:±100ppm/°C;")
      (fields
        (field (name "Manufacturer Part") "0805W8F510JT5E")
        (field (name "Manufacturer") "UNI-ROYAL(厚声)")
      )
      (libsource (lib "easyedapro") (part "0805W8F510JT5E"))
    )
    (comp (ref "R76")
      (value "51Ω")
      (footprint "easyedapro:R0805")
      (description "电阻类型:厚膜电阻;阻值:51Ω;精度:±1%;功率:125mW;最大工作电压:150V;温度系数:±100ppm/°C;")
      (fields
        (field (name "Manufacturer Part") "0805W8F510JT5E")
        (field (name "Manufacturer") "UNI-ROYAL(厚声)")
      )
      (libsource (lib "easyedapro") (part "0805W8F510JT5E"))
    )
    (comp (ref "SW13")
      (value "HX TS3425BA 250gf")
      (footprint "easyedapro:SW-SMD_4P-L4.2-W3.2-P2.15-LS4.6-1")
      (fields (field (name "Manufacturer") "hanxia(韩下)"))
      (libsource (lib "easyedapro") (part "TS3425BA"))
    )
    (comp (ref "SW14")
      (value "HX TS3425BA 250gf")
      (footprint "easyedapro:SW-SMD_4P-L4.2-W3.2-P2.15-LS4.6-1")
      (fields (field (name "Manufacturer") "hanxia(韩下)"))
      (libsource (lib "easyedapro") (part "TS3425BA"))
    )
    (comp (ref "U4")
      (value "SH367303Q/028QY")
      (footprint "easyedapro:QFN-28_L5.0-W5.0-P0.50-TL-EP3.3")
      (libsource (lib "easyedapro") (part "SH367303Q/028QY"))
    )
    (comp (ref "U6")
      (value "WAFER-GH1.25-6PLB")
      (footprint "easyedapro:CONN-SMD_6P-P1.25_XUNPU_WAFER-GH1.25-6PLB")
      (description "插针结构:1x6P;间距:1.25mm;安装方式:立贴;参考系列:GH;总PIN数:6P;排数:1;每排PIN数:6;额定电流:1A;工作温度范围:-25°C~+85°C;")
      (fields (field (name "Manufacturer") "XUNPU(讯普)"))
      (libsource (lib "easyedapro") (part "WAFER-GH1.25-6PLB"))
    )
    (comp (ref "U7")
      (value "GD32E230F8P6TR")
      (footprint "easyedapro:TSSOP-20_L6.5-W4.4-P0.65-LS6.4-BL")
      (description "CPU内核:ARM-M系列;程序存储容量:64KB;RAM总容量:8KB;GPIO端口数量:15;工作电压范围:1.8V~3.6V;CPU最大主频:72MHz;程序存储器类型:FLASH;")
      (fields (field (name "Manufacturer") "GigaDevice(兆易创新)"))
      (libsource (lib "easyedapro") (part "GD32E230F8P6TR"))
    )
    (comp (ref "U9")
      (value "LV2842XLVDDCR")
      (footprint "easyedapro:SOT-23-6_L2.9-W1.6-P0.95-LS2.8-BR")
      (description "功能类型:降压型;输入电压:-;输出电流(最大值):-;")
      (fields (field (name "Manufacturer") "TI(德州仪器)"))
      (libsource (lib "easyedapro") (part "LV2842XLVDDCR"))
    )
    (comp (ref "U10")
      (value "1uH")
      (footprint "easyedapro:L0603")
      (description "电感值:1uH;精度:±10%;额定电流:25mA;饱和电流(Isat):-;直流电阻(DCR):600mΩ;")
      (fields (field (name "Manufacturer Part") "YL160808-1R0K") (field (name "Manufacturer") "YJYCOIN(益嘉源)"))
      (libsource (lib "easyedapro") (part "YL160808-1R0K"))
    )
    (comp (ref "U11")
      (value "π122U31")
      (footprint "easyedapro:SOIC-8_L4.9-W3.9-P1.27-LS6.0-BL")
      (description "应用:-;通道数:2;隔离电压(Viso):3000Vrms;隔离技术:-;")
      (fields (field (name "Manufacturer") "2Pai Semi(荣湃)"))
      (libsource (lib "easyedapro") (part "π122U31"))
    )
    (comp (ref "X1")
      (value "12MHz")
      (footprint "easyedapro:CRYSTAL-SMD_4P-L3.2-W2.5-BL")
      (description "频率:24MHz;频率公差:±20ppm;负载电容:20pF;")
      (fields (field (name "Manufacturer Part") "X322512MSB4SI") (field (name "Manufacturer") "YXC(扬兴晶振)"))
      (libsource (lib "easyedapro") (part "XXHCCLNANF-24MHZ"))
    )
  )
  (nets
    (net (code "1") (name "/ALARM") (class "Default")
      (node (ref "R10") (pin "1") (pinfunction "1_1") (pintype "input"))
      (node (ref "R8") (pin "1") (pinfunction "1_1") (pintype "input"))
    )
    (net (code "2") (name "/BOOT0") (class "Default")
      (node (ref "R54") (pin "2") (pinfunction "2_2") (pintype "input"))
      (node (ref "SW14") (pin "3") (pinfunction "3_3") (pintype "unspecified"))
      (node (ref "SW14") (pin "4") (pinfunction "4_4") (pintype "unspecified"))
      (node (ref "U7") (pin "1") (pinfunction "BOOT0_1") (pintype "input"))
    )
    (net (code "3") (name "/CHG") (class "Default")
      (node (ref "R23") (pin "2") (pinfunction "2_2") (pintype "input"))
      (node (ref "U4") (pin "26") (pinfunction "CHG_26") (pintype "unspecified"))
    )
    (net (code "4") (name "/CHGD") (class "Default")
      (node (ref "R27") (pin "2") (pinfunction "2_2") (pintype "input"))
      (node (ref "U4") (pin "25") (pinfunction "CHGD_25") (pintype "unspecified"))
    )
    (net (code "5") (name "/DSG") (class "Default")
      (node (ref "R24") (pin "2") (pinfunction "2_2") (pintype "input"))
      (node (ref "U4") (pin "28") (pinfunction "DSG_28") (pintype "unspecified"))
    )
    (net (code "6") (name "/DSGD") (class "Default")
      (node (ref "R22") (pin "2") (pinfunction "2_2") (pintype "input"))
      (node (ref "U4") (pin "27") (pinfunction "DSGD_27") (pintype "unspecified"))
    )
    (net (code "7") (name "/LED0") (class "Default")
      (node (ref "KEY1") (pin "5") (pinfunction "A_5") (pintype "input"))
      (node (ref "U7") (pin "7") (pinfunction "PA1_7") (pintype "input"))
    )
    (net (code "8") (name "/LED1") (class "Default")
      (node (ref "R60") (pin "2") (pinfunction "2_2") (pintype "input"))
      (node (ref "U7") (pin "14") (pinfunction "PB1_14") (pintype "input"))
    )
    (net (code "9") (name "/LED2") (class "Default")
      (node (ref "R58") (pin "2") (pinfunction "2_2") (pintype "input"))
      (node (ref "U7") (pin "13") (pinfunction "PA7_13") (pintype "input"))
    )
    (net (code "10") (name "/LED3") (class "Default")
      (node (ref "R62") (pin "2") (pinfunction "2_2") (pintype "input"))
      (node (ref "U7") (pin "12") (pinfunction "PA6_12") (pintype "input"))
    )
    (net (code "11") (name "/LED4") (class "Default")
      (node (ref "R61") (pin "2") (pinfunction "2_2") (pintype "input"))
      (node (ref "U7") (pin "11") (pinfunction "PA5_11") (pintype "input"))
    )
    (net (code "12") (name "/MCUPW_EN") (class "Default")
      (node (ref "U7") (pin "10") (pinfunction "PA4_10") (pintype "input"))
      (node (ref "U9") (pin "4") (pinfunction "SHDN#_4") (pintype "unspecified"))
    )
    (net (code "13") (name "/NRST") (class "Default")
      (node (ref "C26") (pin "2") (pinfunction "2_2") (pintype "input"))
      (node (ref "SW13") (pin "1") (pinfunction "1_1") (pintype "unspecified"))
      (node (ref "SW13") (pin "2") (pinfunction "2_2") (pintype "unspecified"))
      (node (ref "U7") (pin "4") (pinfunction "NRST_4") (pintype "input"))
    )
    (net (code "14") (name "/OSC_IN") (class "Default")
      (node (ref "C27") (pin "2") (pinfunction "2_2") (pintype "input"))
      (node (ref "U7") (pin "2") (pinfunction "OSCIN/PF0_2") (pintype "input"))
      (node (ref "X1") (pin "1") (pinfunction "1_1") (pintype "input"))
    )
    (net (code "15") (name "/OSC_OUT") (class "Default")
      (node (ref "C28") (pin "2") (pinfunction "2_2") (pintype "input"))
      (node (ref "U7") (pin "3") (pinfunction "OSCOUT/PF1_3") (pintype "input"))
      (node (ref "X1") (pin "3") (pinfunction "3_3") (pintype "input"))
    )
    (net (code "16") (name "/PA0") (class "Default")
      (node (ref "KEY1") (pin "1") (pinfunction "3_1") (pintype "input"))
      (node (ref "KEY1") (pin "2") (pinfunction "1_2") (pintype "input"))
      (node (ref "U7") (pin "6") (pinfunction "PA0_6") (pintype "input"))
    )
    (net (code "17") (name "/RESET") (class "Default")
      (node (ref "R11") (pin "1") (pinfunction "1_1") (pintype "input"))
      (node (ref "R9") (pin "1") (pinfunction "1_1") (pintype "input"))
    )
    (net (code "18") (name "/SCL") (class "Default")
      (node (ref "R3") (pin "1") (pinfunction "1_1") (pintype "input"))
      (node (ref "R6") (pin "1") (pinfunction "1_1") (pintype "input"))
      (node (ref "U7") (pin "17") (pinfunction "PA9(PA11)_17") (pintype "input"))
    )
    (net (code "19") (name "/SDA") (class "Default")
      (node (ref "R4") (pin "1") (pinfunction "1_1") (pintype "input"))
      (node (ref "R5") (pin "1") (pinfunction "1_1") (pintype "input"))
      (node (ref "U7") (pin "18") (pinfunction "PA10(PA12)_18") (pintype "input"))
    )
    (net (code "20") (name "/SWCLK") (class "Default")
      (node (ref "CN10") (pin "1") (pinfunction "1_1") (pintype "unspecified"))
      (node (ref "U7") (pin "20") (pinfunction "PA14_20") (pintype "input"))
    )
    (net (code "21") (name "/SWDIO") (class "Default")
      (node (ref "CN10") (pin "2") (pinfunction "2_2") (pintype "unspecified"))
      (node (ref "U7") (pin "19") (pinfunction "PA13_19") (pintype "input"))
    )
    (net (code "22") (name "/USART_RX") (class "Default")
      (node (ref "R72") (pin "2") (pinfunction "2_2") (pintype "input"))
      (node (ref "U7") (pin "9") (pinfunction "PA3_9") (pintype "input"))
    )
    (net (code "23") (name "/USART_RX2") (class "Default")
      (node (ref "H9") (pin "6") (pinfunction "+_6") (pintype "input"))
      (node (ref "R74") (pin "2") (pinfunction "2_2") (pintype "input"))
    )
    (net (code "24") (name "/USART_TX") (class "Default")
      (node (ref "R71") (pin "2") (pinfunction "2_2") (pintype "input"))
      (node (ref "U7") (pin "8") (pinfunction "PA2_8") (pintype "input"))
    )
    (net (code "25") (name "/USART_TX2") (class "Default")
      (node (ref "H9") (pin "4") (pinfunction "+_4") (pintype "input"))
      (node (ref "R73") (pin "2") (pinfunction "2_2") (pintype "input"))
    )
    (net (code "26") (name "GND") (class "Default")
      (node (ref "C1") (pin "2") (pinfunction "2_2") (pintype "input"))
      (node (ref "C10") (pin "1") (pinfunction "1_1") (pintype "input"))
      (node (ref "C11") (pin "1") (pinfunction "1_1") (pintype "input"))
      (node (ref "C13") (pin "1") (pinfunction "1_1") (pintype "input"))
      (node (ref "C14") (pin "1") (pinfunction "1_1") (pintype "input"))
      (node (ref "C17") (pin "1") (pinfunction "1_1") (pintype "input"))
      (node (ref "C19") (pin "1") (pinfunction "1_1") (pintype "input"))
      (node (ref "C2") (pin "2") (pinfunction "2_2") (pintype "input"))
      (node (ref "C24") (pin "1") (pinfunction "1_1") (pintype "input"))
      (node (ref "C25") (pin "1") (pinfunction "1_1") (pintype "input"))
      (node (ref "C26") (pin "1") (pinfunction "1_1") (pintype "input"))
      (node (ref "C27") (pin "1") (pinfunction "1_1") (pintype "input"))
      (node (ref "C28") (pin "1") (pinfunction "1_1") (pintype "input"))
      (node (ref "C29") (pin "2") (pinfunction "2_2") (pintype "input"))
      (node (ref "C3") (pin "1") (pinfunction "1_1") (pintype "input"))
      (node (ref "C31") (pin "2") (pinfunction "2_2") (pintype "input"))
      (node (ref "C32") (pin "2") (pinfunction "2_2") (pintype "input"))
      (node (ref "C33") (pin "1") (pinfunction "1_1") (pintype "input"))
      (node (ref "C4") (pin "1") (pinfunction "1_1") (pintype "input"))
      (node (ref "C6") (pin "1") (pinfunction "1_1") (pintype "input"))
      (node (ref "C7") (pin "1") (pinfunction "1_1") (pintype "input"))
      (node (ref "C8") (pin "1") (pinfunction "1_1") (pintype "input"))
      (node (ref "C9") (pin "1") (pinfunction "1_1") (pintype "input"))
      (node (ref "CN10") (pin "3") (pinfunction "3_3") (pintype "unspecified"))
      (node (ref "CN10") (pin "5") (pinfunction "5_5") (pintype "unspecified"))
      (node (ref "CN10") (pin "6") (pinfunction "6_6") (pintype "unspecified"))
      (node (ref "D4") (pin "2") (pinfunction "A_2") (pintype "unspecified"))
      (node (ref "D50") (pin "2") (pinfunction "A_2") (pintype "unspecified"))
      (node (ref "LED1") (pin "1") (pinfunction "K_1") (pintype "unspecified"))
      (node (ref "LED2") (pin "1") (pinfunction "K_1") (pintype "unspecified"))
      (node (ref "LED3") (pin "1") (pinfunction "K_1") (pintype "unspecified"))
      (node (ref "LED4") (pin "1") (pinfunction "K_1") (pintype "unspecified"))
      (node (ref "R1") (pin "1") (pinfunction "1_1") (pintype "input"))
      (node (ref "R14") (pin "1") (pinfunction "1_1") (pintype "unspecified"))
      (node (ref "R15") (pin "1") (pinfunction "1_1") (pintype "input"))
      (node (ref "R16") (pin "1") (pinfunction "1_1") (pintype "unspecified"))
      (node (ref "R17") (pin "1") (pinfunction "1_1") (pintype "input"))
      (node (ref "R28") (pin "1") (pinfunction "1_1") (pintype "input"))
      (node (ref "R54") (pin "1") (pinfunction "1_1") (pintype "input"))
      (node (ref "R57") (pin "1") (pinfunction "1_1") (pintype "input"))
      (node (ref "R69") (pin "2") (pinfunction "2_2") (pintype "input"))
      (node (ref "R70") (pin "2") (pinfunction "2_2") (pintype "input"))
      (node (ref "SW13") (pin "3") (pinfunction "3_3") (pintype "unspecified"))
      (node (ref "SW13") (pin "4") (pinfunction "4_4") (pintype "unspecified"))
      (node (ref "U11") (pin "4") (pinfunction "GND1_4") (pintype "unspecified"))
      (node (ref "U4") (pin "11") (pinfunction "GND_11") (pintype "unspecified"))
      (node (ref "U4") (pin "29") (pinfunction "EP_29") (pintype "unspecified"))
      (node (ref "U7") (pin "15") (pinfunction "Vss_15") (pintype "input"))
      (node (ref "U9") (pin "2") (pinfunction "GND_2") (pintype "unspecified"))
      (node (ref "X1") (pin "2") (pinfunction "GND_2") (pintype "input"))
      (node (ref "X1") (pin "4") (pinfunction "GND_4") (pintype "input"))
    )
    (net (code "27") (name "MCU+3.3V") (class "Default")
      (node (ref "C17") (pin "2") (pinfunction "2_2") (pintype "input"))
      (node (ref "C19") (pin "2") (pinfunction "2_2") (pintype "input"))
      (node (ref "C24") (pin "2") (pinfunction "2_2") (pintype "input"))
      (node (ref "C25") (pin "2") (pinfunction "2_2") (pintype "input"))
      (node (ref "C31") (pin "1") (pinfunction "1_1") (pintype "input"))
      (node (ref "C32") (pin "1") (pinfunction "1_1") (pintype "input"))
      (node (ref "CN10") (pin "4") (pinfunction "4_4") (pintype "unspecified"))
      (node (ref "D3") (pin "1") (pinfunction "K_1") (pintype "unspecified"))
      (node (ref "KEY1") (pin "3") (pinfunction "4_3") (pintype "input"))
      (node (ref "KEY1") (pin "4") (pinfunction "2_4") (pintype "input"))
      (node (ref "L1") (pin "1") (pinfunction "1_1") (pintype "unspecified"))
      (node (ref "R55") (pin "1") (pinfunction "1_1") (pintype "input"))
      (node (ref "R56") (pin "2") (pinfunction "2_2") (pintype "input"))
      (node (ref "U11") (pin "1") (pinfunction "VDD1_1") (pintype "unspecified"))
      (node (ref "U7") (pin "16") (pinfunction "VDD_16") (pintype "input"))
      (node (ref "U7") (pin "5") (pinfunction "VDDA_5") (pintype "input"))
    )
    (net (code "28") (name "Net-(C3-Pad2)") (class "Default")
      (node (ref "C3") (pin "2") (pinfunction "2_2") (pintype "input"))
      (node (ref "R13") (pin "1") (pinfunction "1_1") (pintype "input"))
      (node (ref "R15") (pin "2") (pinfunction "2_2") (pintype "input"))
      (node (ref "R16") (pin "2") (pinfunction "2_2") (pintype "unspecified"))
    )
    (net (code "29") (name "Net-(C4-Pad2)") (class "Default")
      (node (ref "C4") (pin "2") (pinfunction "2_2") (pintype "input"))
      (node (ref "R12") (pin "1") (pinfunction "1_1") (pintype "input"))
      (node (ref "R14") (pin "2") (pinfunction "2_2") (pintype "unspecified"))
      (node (ref "R17") (pin "2") (pinfunction "2_2") (pintype "input"))
    )
    (net (code "30") (name "Net-(C34-Pad1)") (class "Default")
      (node (ref "C34") (pin "1") (pinfunction "1_1") (pintype "input"))
      (node (ref "C35") (pin "2") (pinfunction "2_2") (pintype "input"))
    )
    (net (code "31") (name "Net-(D1-A)") (class "Default")
      (node (ref "C14") (pin "2") (pinfunction "2_2") (pintype "input"))
      (node (ref "D1") (pin "2") (pinfunction "A_2") (pintype "unspecified"))
      (node (ref "R75") (pin "1") (pinfunction "1_1") (pintype "input"))
    )
    (net (code "32") (name "Net-(D1-K)") (class "Default")
      (node (ref "D1") (pin "1") (pinfunction "K_1") (pintype "unspecified"))
      (node (ref "R76") (pin "2") (pinfunction "2_2") (pintype "input"))
    )
    (net (code "33") (name "Net-(D2-A)") (class "Default")
      (node (ref "C35") (pin "1") (pinfunction "1_1") (pintype "input"))
      (node (ref "D2") (pin "2") (pinfunction "A_2") (pintype "unspecified"))
      (node (ref "P1") (pin "1") (pinfunction "1_1") (pintype "unspecified"))
      (node (ref "Q11") (pin "1") (pinfunction "S_1") (pintype "unspecified"))
      (node (ref "Q11") (pin "2") (pinfunction "S_2") (pintype "unspecified"))
      (node (ref "Q11") (pin "3") (pinfunction "S_3") (pintype "unspecified"))
      (node (ref "R26") (pin "1") (pinfunction "1_1") (pintype "input"))
      (node (ref "R27") (pin "1") (pinfunction "1_1") (pintype "input"))
    )
    (net (code "34") (name "Net-(D4-K)") (class "Default")
      (node (ref "C30") (pin "1") (pinfunction "1_1") (pintype "input"))
      (node (ref "D4") (pin "1") (pinfunction "K_1") (pintype "unspecified"))
      (node (ref "L1") (pin "2") (pinfunction "2_2") (pintype "unspecified"))
      (node (ref "U9") (pin "6") (pinfunction "SW_6") (pintype "unspecified"))
    )
    (net (code "35") (name "Net-(D6-A)") (class "Default")
      (node (ref "D6") (pin "2") (pinfunction "A_2") (pintype "unspecified"))
      (node (ref "R73") (pin "1") (pinfunction "1_1") (pintype "input"))
      (node (ref "U11") (pin "6") (pinfunction "VOB_6") (pintype "unspecified"))
    )
    (net (code "36") (name "Net-(D7-A)") (class "Default")
      (node (ref "D7") (pin "2") (pinfunction "A_2") (pintype "unspecified"))
      (node (ref "R74") (pin "1") (pinfunction "1_1") (pintype "input"))
      (node (ref "U11") (pin "7") (pinfunction "VIA_7") (pintype "unspecified"))
    )
    (net (code "37") (name "Net-(D50-C)") (class "Default")
      (node (ref "C33") (pin "2") (pinfunction "2_2") (pintype "input"))
      (node (ref "D50") (pin "1") (pinfunction "C_1") (pintype "unspecified"))
      (node (ref "R76") (pin "1") (pinfunction "1_1") (pintype "input"))
      (node (ref "U4") (pin "17") (pinfunction "VDD_17") (pintype "unspecified"))
    )
    (net (code "38") (name "Net-(KEY1-C)") (class "Default")
      (node (ref "KEY1") (pin "6") (pinfunction "C_6") (pintype "input"))
      (node (ref "R70") (pin "1") (pinfunction "1_1") (pintype "input"))
    )
    (net (code "39") (name "Net-(LED1-A)") (class "Default")
      (node (ref "LED1") (pin "2") (pinfunction "A_2") (pintype "unspecified"))
      (node (ref "R60") (pin "1") (pinfunction "1_1") (pintype "input"))
    )
    (net (code "40") (name "Net-(LED2-A)") (class "Default")
      (node (ref "LED2") (pin "2") (pinfunction "A_2") (pintype "unspecified"))
      (node (ref "R58") (pin "1") (pinfunction "1_1") (pintype "input"))
    )
    (net (code "41") (name "Net-(LED3-A)") (class "Default")
      (node (ref "LED3") (pin "2") (pinfunction "A_2") (pintype "unspecified"))
      (node (ref "R62") (pin "1") (pinfunction "1_1") (pintype "input"))
    )
    (net (code "42") (name "Net-(LED4-A)") (class "Default")
      (node (ref "LED4") (pin "2") (pinfunction "A_2") (pintype "unspecified"))
      (node (ref "R61") (pin "1") (pinfunction "1_1") (pintype "input"))
    )
    (net (code "43") (name "Net-(Q6-B)") (class "Default")
      (node (ref "Q6") (pin "1") (pinfunction "B_1") (pintype "unspecified"))
      (node (ref "R36") (pin "2") (pinfunction "2_2") (pintype "input"))
    )
    (net (code "44") (name "Net-(Q6-C)") (class "Default")
      (node (ref "Q6") (pin "3") (pinfunction "C_3") (pintype "unspecified"))
      (node (ref "R66") (pin "1") (pinfunction "1_1") (pintype "input"))
    )
    (net (code "45") (name "Net-(Q6-E)") (class "Default")
      (node (ref "Q6") (pin "2") (pinfunction "E_2") (pintype "unspecified"))
      (node (ref "R35") (pin "2") (pinfunction "2_2") (pintype "input"))
      (node (ref "R65") (pin "2") (pinfunction "2_2") (pintype "input"))
      (node (ref "U6") (pin "3") (pinfunction "3_3") (pintype "unspecified"))
    )
    (net (code "46") (name "Net-(Q7-B)") (class "Default")
      (node (ref "Q7") (pin "1") (pinfunction "B_1") (pintype "unspecified"))
      (node (ref "R38") (pin "2") (pinfunction "2_2") (pintype "input"))
    )
    (net (code "47") (name "Net-(Q7-C)") (class "Default")
      (node (ref "Q7") (pin "3") (pinfunction "C_3") (pintype "unspecified"))
      (node (ref "R67") (pin "1") (pinfunction "1_1") (pintype "input"))
    )
    (net (code "48") (name "Net-(Q7-E)") (class "Default")
      (node (ref "Q7") (pin "2") (pinfunction "E_2") (pintype "unspecified"))
      (node (ref "R37") (pin "2") (pinfunction "2_2") (pintype "input"))
      (node (ref "R66") (pin "2") (pinfunction "2_2") (pintype "input"))
      (node (ref "U6") (pin "4") (pinfunction "4_4") (pintype "unspecified"))
    )
    (net (code "49") (name "Net-(Q8-B)") (class "Default")
      (node (ref "Q8") (pin "1") (pinfunction "B_1") (pintype "unspecified"))
      (node (ref "R40") (pin "2") (pinfunction "2_2") (pintype "input"))
    )
    (net (code "50") (name "Net-(Q8-C)") (class "Default")
      (node (ref "Q8") (pin "3") (pinfunction "C_3") (pintype "unspecified"))
      (node (ref "R68") (pin "1") (pinfunction "1_1") (pintype "input"))
    )
    (net (code "51") (name "Net-(Q8-E)") (class "Default")
      (node (ref "Q8") (pin "2") (pinfunction "E_2") (pintype "unspecified"))
      (node (ref "R39") (pin "2") (pinfunction "2_2") (pintype "input"))
      (node (ref "R67") (pin "2") (pinfunction "2_2") (pintype "input"))
      (node (ref "U6") (pin "5") (pinfunction "5_5") (pintype "unspecified"))
    )
    (net (code "52") (name "Net-(Q9-B)") (class "Default")
      (node (ref "Q9") (pin "1") (pinfunction "B_1") (pintype "unspecified"))
      (node (ref "R34") (pin "2") (pinfunction "2_2") (pintype "input"))
    )
    (net (code "53") (name "Net-(Q9-C)") (class "Default")
      (node (ref "Q9") (pin "3") (pinfunction "C_3") (pintype "unspecified"))
      (node (ref "R65") (pin "1") (pinfunction "1_1") (pintype "input"))
    )
    (net (code "54") (name "Net-(Q9-E)") (class "Default")
      (node (ref "Q9") (pin "2") (pinfunction "E_2") (pintype "unspecified"))
      (node (ref "R33") (pin "2") (pinfunction "2_2") (pintype "input"))
      (node (ref "R64") (pin "2") (pinfunction "2_2") (pintype "input"))
      (node (ref "U6") (pin "2") (pinfunction "2_2") (pintype "unspecified"))
    )
    (net (code "55") (name "Net-(Q10-B)") (class "Default")
      (node (ref "Q10") (pin "1") (pinfunction "B_1") (pintype "unspecified"))
      (node (ref "R32") (pin "2") (pinfunction "2_2") (pintype "input"))
    )
    (net (code "56") (name "Net-(Q10-C)") (class "Default")
      (node (ref "Q10") (pin "3") (pinfunction "C_3") (pintype "unspecified"))
      (node (ref "R64") (pin "1") (pinfunction "1_1") (pintype "input"))
    )
    (net (code "57") (name "Net-(Q11-D-Pad5)") (class "Default")
      (node (ref "Q11") (pin "5") (pinfunction "D_5") (pintype "unspecified"))
      (node (ref "Q11") (pin "6") (pinfunction "D_6") (pintype "unspecified"))
      (node (ref "Q11") (pin "7") (pinfunction "D_7") (pintype "unspecified"))
      (node (ref "Q11") (pin "8") (pinfunction "D_8") (pintype "unspecified"))
      (node (ref "Q12") (pin "5") (pinfunction "D_5") (pintype "unspecified"))
      (node (ref "Q12") (pin "6") (pinfunction "D_6") (pintype "unspecified"))
      (node (ref "Q12") (pin "7") (pinfunction "D_7") (pintype "unspecified"))
      (node (ref "Q12") (pin "8") (pinfunction "D_8") (pintype "unspecified"))
      (node (ref "R22") (pin "1") (pinfunction "1_1") (pintype "input"))
    )
    (net (code "58") (name "Net-(Q11-G)") (class "Default")
      (node (ref "Q11") (pin "4") (pinfunction "G_4") (pintype "unspecified"))
      (node (ref "R23") (pin "1") (pinfunction "1_1") (pintype "input"))
      (node (ref "R26") (pin "2") (pinfunction "2_2") (pintype "input"))
    )
    (net (code "59") (name "Net-(Q12-G)") (class "Default")
      (node (ref "Q12") (pin "4") (pinfunction "G_4") (pintype "unspecified"))
      (node (ref "R24") (pin "1") (pinfunction "1_1") (pintype "input"))
      (node (ref "R25") (pin "2") (pinfunction "2_2") (pintype "input"))
    )
    (net (code "60") (name "Net-(Q12-S-Pad1)") (class "Default")
      (node (ref "Q12") (pin "1") (pinfunction "S_1") (pintype "unspecified"))
      (node (ref "Q12") (pin "2") (pinfunction "S_2") (pintype "unspecified"))
      (node (ref "Q12") (pin "3") (pinfunction "S_3") (pintype "unspecified"))
      (node (ref "R18") (pin "1") (pinfunction "1_1") (pintype "unspecified"))
      (node (ref "R21") (pin "1") (pinfunction "1_1") (pintype "input"))
      (node (ref "R25") (pin "1") (pinfunction "1_1") (pintype "input"))
    )
    (net (code "61") (name "Net-(R55-Pad2)") (class "Default")
      (node (ref "R55") (pin "2") (pinfunction "2_2") (pintype "input"))
      (node (ref "SW14") (pin "1") (pinfunction "1_1") (pintype "unspecified"))
      (node (ref "SW14") (pin "2") (pinfunction "2_2") (pintype "unspecified"))
    )
    (net (code "62") (name "Net-(U4-ALARM)") (class "Default")
      (node (ref "R8") (pin "2") (pinfunction "2_2") (pintype "input"))
      (node (ref "U4") (pin "5") (pinfunction "ALARM_5") (pintype "unspecified"))
    )
    (net (code "63") (name "Net-(U4-CTLD)") (class "Default")
      (node (ref "R2") (pin "1") (pinfunction "1_1") (pintype "input"))
      (node (ref "U4") (pin "4") (pinfunction "CTLD_4") (pintype "unspecified"))
    )
    (net (code "64") (name "Net-(U4-RESET{slash}PF)") (class "Default")
      (node (ref "R9") (pin "2") (pinfunction "2_2") (pintype "input"))
      (node (ref "U4") (pin "6") (pinfunction "RESET/PF_6") (pintype "unspecified"))
    )
    (net (code "65") (name "Net-(U4-RS1)") (class "Default")
      (node (ref "C5") (pin "1") (pinfunction "1_1") (pintype "input"))
      (node (ref "C7") (pin "2") (pinfunction "2_2") (pintype "input"))
      (node (ref "R20") (pin "2") (pinfunction "2_2") (pintype "input"))
      (node (ref "U4") (pin "8") (pinfunction "RS1_8") (pintype "unspecified"))
    )
    (net (code "66") (name "Net-(U4-RS2)") (class "Default")
      (node (ref "C5") (pin "2") (pinfunction "2_2") (pintype "input"))
      (node (ref "C6") (pin "2") (pinfunction "2_2") (pintype "input"))
      (node (ref "R21") (pin "2") (pinfunction "2_2") (pintype "input"))
      (node (ref "U4") (pin "7") (pinfunction "RS2_7") (pintype "unspecified"))
    )
    (net (code "67") (name "Net-(U4-SCL)") (class "Default")
      (node (ref "R6") (pin "2") (pinfunction "2_2") (pintype "input"))
      (node (ref "U4") (pin "3") (pinfunction "SCL_3") (pintype "unspecified"))
    )
    (net (code "68") (name "Net-(U4-SDA)") (class "Default")
      (node (ref "R5") (pin "2") (pinfunction "2_2") (pintype "input"))
      (node (ref "U4") (pin "2") (pinfunction "SDA_2") (pintype "unspecified"))
    )
    (net (code "69") (name "Net-(U4-TS1)") (class "Default")
      (node (ref "R13") (pin "2") (pinfunction "2_2") (pintype "input"))
      (node (ref "U4") (pin "10") (pinfunction "TS1_10") (pintype "unspecified"))
    )
    (net (code "70") (name "Net-(U4-TS2)") (class "Default")
      (node (ref "R12") (pin "2") (pinfunction "2_2") (pintype "input"))
      (node (ref "U4") (pin "9") (pinfunction "TS2_9") (pintype "unspecified"))
    )
    (net (code "71") (name "Net-(U4-VC1)") (class "Default")
      (node (ref "C13") (pin "2") (pinfunction "2_2") (pintype "input"))
      (node (ref "R1") (pin "2") (pinfunction "2_2") (pintype "input"))
      (node (ref "R39") (pin "1") (pinfunction "1_1") (pintype "input"))
      (node (ref "R40") (pin "1") (pinfunction "1_1") (pintype "input"))
      (node (ref "U4") (pin "12") (pinfunction "VC1_12") (pintype "unspecified"))
    )
    (net (code "72") (name "Net-(U4-VC2)") (class "Default")
      (node (ref "C8") (pin "2") (pinfunction "2_2") (pintype "input"))
      (node (ref "R28") (pin "2") (pinfunction "2_2") (pintype "input"))
      (node (ref "R37") (pin "1") (pinfunction "1_1") (pintype "input"))
      (node (ref "R38") (pin "1") (pinfunction "1_1") (pintype "input"))
      (node (ref "U4") (pin "13") (pinfunction "VC2_13") (pintype "unspecified"))
    )
    (net (code "73") (name "Net-(U4-VC3)") (class "Default")
      (node (ref "C9") (pin "2") (pinfunction "2_2") (pintype "input"))
      (node (ref "R35") (pin "1") (pinfunction "1_1") (pintype "input"))
      (node (ref "R36") (pin "1") (pinfunction "1_1") (pintype "input"))
      (node (ref "U4") (pin "14") (pinfunction "VC3_14") (pintype "unspecified"))
    )
    (net (code "74") (name "Net-(U4-VC4)") (class "Default")
      (node (ref "C10") (pin "2") (pinfunction "2_2") (pintype "input"))
      (node (ref "R33") (pin "1") (pinfunction "1_1") (pintype "input"))
      (node (ref "R34") (pin "1") (pinfunction "1_1") (pintype "input"))
      (node (ref "U4") (pin "15") (pinfunction "VC4_15") (pintype "unspecified"))
    )
    (net (code "75") (name "Net-(U4-VC5)") (class "Default")
      (node (ref "C11") (pin "2") (pinfunction "2_2") (pintype "input"))
      (node (ref "R31") (pin "1") (pinfunction "1_1") (pintype "input"))
      (node (ref "R32") (pin "1") (pinfunction "1_1") (pintype "input"))
      (node (ref "U4") (pin "16") (pinfunction "VC5_16") (pintype "unspecified"))
    )
    (net (code "76") (name "Net-(U9-CB)") (class "Default")
      (node (ref "C30") (pin "2") (pinfunction "2_2") (pintype "input"))
      (node (ref "U9") (pin "1") (pinfunction "CB_1") (pintype "unspecified"))
    )
    (net (code "77") (name "Net-(U9-FB)") (class "Default")
      (node (ref "R56") (pin "1") (pinfunction "1_1") (pintype "input"))
      (node (ref "R57") (pin "2") (pinfunction "2_2") (pintype "input"))
      (node (ref "U9") (pin "3") (pinfunction "FB_3") (pintype "unspecified"))
    )
    (net (code "78") (name "Net-(U9-VIN)") (class "Default")
      (node (ref "C29") (pin "1") (pinfunction "1_1") (pintype "input"))
      (node (ref "U10") (pin "1") (pinfunction "1_1") (pintype "unspecified"))
      (node (ref "U9") (pin "5") (pinfunction "VIN_5") (pintype "unspecified"))
    )
    (net (code "79") (name "Net-(U11-VIB)") (class "Default")
      (node (ref "R72") (pin "1") (pinfunction "1_1") (pintype "input"))
      (node (ref "U11") (pin "3") (pinfunction "VIB_3") (pintype "unspecified"))
    )
    (net (code "80") (name "Net-(U11-VOA)") (class "Default")
      (node (ref "R71") (pin "1") (pinfunction "1_1") (pintype "input"))
      (node (ref "U11") (pin "2") (pinfunction "VOA_2") (pintype "unspecified"))
    )
    (net (code "81") (name "POGND") (class "Default")
      (node (ref "H9") (pin "1") (pinfunction "-_1") (pintype "input"))
      (node (ref "R18") (pin "2") (pinfunction "2_2") (pintype "unspecified"))
      (node (ref "R20") (pin "1") (pinfunction "1_1") (pintype "input"))
      (node (ref "R68") (pin "2") (pinfunction "2_2") (pintype "input"))
      (node (ref "R69") (pin "1") (pinfunction "1_1") (pintype "input"))
      (node (ref "U6") (pin "6") (pinfunction "6_6") (pintype "unspecified"))
    )
    (net (code "82") (name "S+3.3V") (class "Default")
      (node (ref "C36") (pin "2") (pinfunction "2_2") (pintype "input"))
      (node (ref "D51") (pin "1") (pinfunction "C_1") (pintype "input"))
      (node (ref "D6") (pin "1") (pinfunction "K_1") (pintype "unspecified"))
      (node (ref "D7") (pin "1") (pinfunction "K_1") (pintype "unspecified"))
      (node (ref "H9") (pin "5") (pinfunction "+_5") (pintype "input"))
      (node (ref "U11") (pin "8") (pinfunction "VDD2_8") (pintype "unspecified"))
    )
    (net (code "83") (name "SGND") (class "Default")
      (node (ref "C36") (pin "1") (pinfunction "1_1") (pintype "input"))
      (node (ref "D51") (pin "2") (pinfunction "A_2") (pintype "input"))
      (node (ref "H9") (pin "3") (pinfunction "+_3") (pintype "input"))
      (node (ref "U11") (pin "5") (pinfunction "GND2_5") (pintype "unspecified"))
    )
    (net (code "84") (name "SH_+3.3V") (class "Default")
      (node (ref "C1") (pin "1") (pinfunction "1_1") (pintype "input"))
      (node (ref "C2") (pin "1") (pinfunction "1_1") (pintype "input"))
      (node (ref "D3") (pin "2") (pinfunction "A_2") (pintype "unspecified"))
      (node (ref "R10") (pin "2") (pinfunction "2_2") (pintype "input"))
      (node (ref "R11") (pin "2") (pinfunction "2_2") (pintype "input"))
      (node (ref "R2") (pin "2") (pinfunction "2_2") (pintype "input"))
      (node (ref "R3") (pin "2") (pinfunction "2_2") (pintype "input"))
      (node (ref "R4") (pin "2") (pinfunction "2_2") (pintype "input"))
      (node (ref "U4") (pin "1") (pinfunction "V33_1") (pintype "unspecified"))
    )
    (net (code "85") (name "VBAT+") (class "Default")
      (node (ref "C34") (pin "2") (pinfunction "2_2") (pintype "input"))
      (node (ref "D2") (pin "1") (pinfunction "K_1") (pintype "unspecified"))
      (node (ref "H9") (pin "2") (pinfunction "+_2") (pintype "input"))
      (node (ref "P2") (pin "1") (pinfunction "1_1") (pintype "unspecified"))
      (node (ref "Q10") (pin "2") (pinfunction "E_2") (pintype "unspecified"))
      (node (ref "R31") (pin "2") (pinfunction "2_2") (pintype "input"))
      (node (ref "R75") (pin "2") (pinfunction "2_2") (pintype "input"))
      (node (ref "U10") (pin "2") (pinfunction "2_2") (pintype "unspecified"))
      (node (ref "U6") (pin "1") (pinfunction "1_1") (pintype "unspecified"))
    )
    (net (code "86") (name "unconnected-(U4-NC-Pad18)") (class "Default")
      (node (ref "U4") (pin "18") (pinfunction "NC_18") (pintype "unspecified+no_connect"))
    )
    (net (code "87") (name "unconnected-(U4-NC-Pad19)") (class "Default")
      (node (ref "U4") (pin "19") (pinfunction "NC_19") (pintype "unspecified+no_connect"))
    )
    (net (code "88") (name "unconnected-(U4-NC-Pad20)") (class "Default")
      (node (ref "U4") (pin "20") (pinfunction "NC_20") (pintype "unspecified+no_connect"))
    )
    (net (code "89") (name "unconnected-(U4-NC-Pad21)") (class "Default")
      (node (ref "U4") (pin "21") (pinfunction "NC_21") (pintype "unspecified+no_connect"))
    )
    (net (code "90") (name "unconnected-(U4-NC-Pad22)") (class "Default")
      (node (ref "U4") (pin "22") (pinfunction "NC_22") (pintype "unspecified+no_connect"))
    )
    (net (code "91") (name "unconnected-(U4-NC-Pad23)") (class "Default")
      (node (ref "U4") (pin "23") (pinfunction "NC_23") (pintype "unspecified+no_connect"))
    )
    (net (code "92") (name "unconnected-(U4-NC-Pad24)") (class "Default")
      (node (ref "U4") (pin "24") (pinfunction "NC_24") (pintype "unspecified+no_connect"))
    )
    (net (code "93") (name "unconnected-(U6-Pad7)") (class "Default")
      (node (ref "U6") (pin "7") (pinfunction "7_7") (pintype "unspecified"))
    )
    (net (code "94") (name "unconnected-(U6-Pad8)") (class "Default")
      (node (ref "U6") (pin "8") (pinfunction "8_8") (pintype "unspecified"))
    )
  )
)
